# Sheet1.net
KiCad netlist of a schematic drawn in Altium Designer
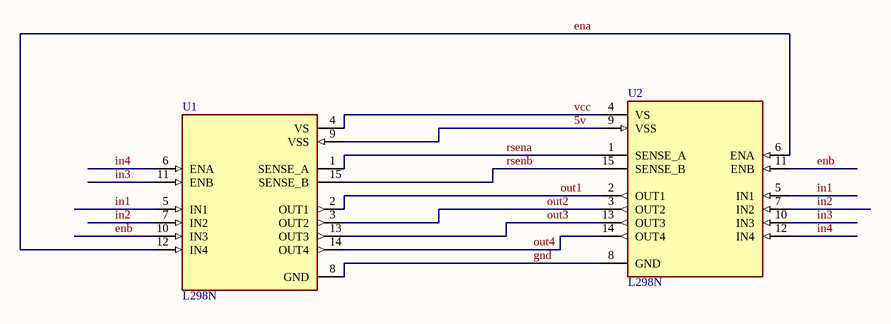
[diagram p0: Sheet1.SchDoc]

(export (version "E")
  (design (tool "Eeschema 10.0.6"))
  (components
    (comp (ref "U1")
      (value "L298N")
      (footprint "l298n:l298n")
      (description "Dual Full Bridge Motor Driver 15-Pin(15+Tab) MULTIWATT V Tube")
      (libsource (lib "drajver") (part "L298N"))
    )
    (comp (ref "U2")
      (value "L298N")
      (footprint "l298n:l298n")
      (description "Dual Full Bridge Motor Driver 15-Pin(15+Tab) MULTIWATT V Tube")
      (libsource (lib "") (part "L298N_1"))
    )
  )
  (nets
    (net (code "1") (name "/5v") (class "Default")
      (node (ref "U1") (pin "9") (pinfunction "VSS_9") (pintype "input"))
      (node (ref "U2") (pin "9") (pinfunction "VSS_9") (pintype "input"))
    )
    (net (code "2") (name "/ena") (class "Default")
      (node (ref "U1") (pin "12") (pinfunction "IN4_12") (pintype "input"))
      (node (ref "U2") (pin "6") (pinfunction "ENA_6") (pintype "input"))
    )
    (net (code "3") (name "/enb") (class "Default")
      (node (ref "U1") (pin "10") (pinfunction "IN3_10") (pintype "input"))
      (node (ref "U2") (pin "11") (pinfunction "ENB_11") (pintype "input"))
    )
    (net (code "4") (name "/gnd") (class "Default")
      (node (ref "U1") (pin "8") (pinfunction "GND_8") (pintype "power_in"))
      (node (ref "U2") (pin "8") (pinfunction "GND_8") (pintype "power_in"))
    )
    (net (code "5") (name "/in1") (class "Default")
      (node (ref "U1") (pin "5") (pinfunction "IN1_5") (pintype "input"))
      (node (ref "U2") (pin "5") (pinfunction "IN1_5") (pintype "input"))
    )
    (net (code "6") (name "/in2") (class "Default")
      (node (ref "U1") (pin "7") (pinfunction "IN2_7") (pintype "input"))
      (node (ref "U2") (pin "7") (pinfunction "IN2_7") (pintype "input"))
    )
    (net (code "7") (name "/in3") (class "Default")
      (node (ref "U1") (pin "11") (pinfunction "ENB_11") (pintype "input"))
      (node (ref "U2") (pin "10") (pinfunction "IN3_10") (pintype "input"))
    )
    (net (code "8") (name "/in4") (class "Default")
      (node (ref "U1") (pin "6") (pinfunction "ENA_6") (pintype "input"))
      (node (ref "U2") (pin "12") (pinfunction "IN4_12") (pintype "input"))
    )
    (net (code "9") (name "/out1") (class "Default")
      (node (ref "U1") (pin "2") (pinfunction "OUT1_2") (pintype "output"))
      (node (ref "U2") (pin "2") (pinfunction "OUT1_2") (pintype "output"))
    )
    (net (code "10") (name "/out2") (class "Default")
      (node (ref "U1") (pin "3") (pinfunction "OUT2_3") (pintype "output"))
      (node (ref "U2") (pin "3") (pinfunction "OUT2_3") (pintype "output"))
    )
    (net (code "11") (name "/out3") (class "Default")
      (node (ref "U1") (pin "13") (pinfunction "OUT3_13") (pintype "output"))
      (node (ref "U2") (pin "13") (pinfunction "OUT3_13") (pintype "output"))
    )
    (net (code "12") (name "/out4") (class "Default")
      (node (ref "U1") (pin "14") (pinfunction "OUT4_14") (pintype "output"))
      (node (ref "U2") (pin "14") (pinfunction "OUT4_14") (pintype "output"))
    )
    (net (code "13") (name "/rsena") (class "Default")
      (node (ref "U1") (pin "1") (pinfunction "SENSE_A_1") (pintype "passive"))
      (node (ref "U2") (pin "1") (pinfunction "SENSE_A_1") (pintype "passive"))
    )
    (net (code "14") (name "/rsenb") (class "Default")
      (node (ref "U1") (pin "15") (pinfunction "SENSE_B_15") (pintype "passive"))
      (node (ref "U2") (pin "15") (pinfunction "SENSE_B_15") (pintype "passive"))
    )
    (net (code "15") (name "/vcc") (class "Default")
      (node (ref "U1") (pin "4") (pinfunction "VS_4") (pintype "power_in"))
      (node (ref "U2") (pin "4") (pinfunction "VS_4") (pintype "power_in"))
    )
  )
)
